# 2_MCU.net
KiCad netlist of a schematic drawn in Altium Designer
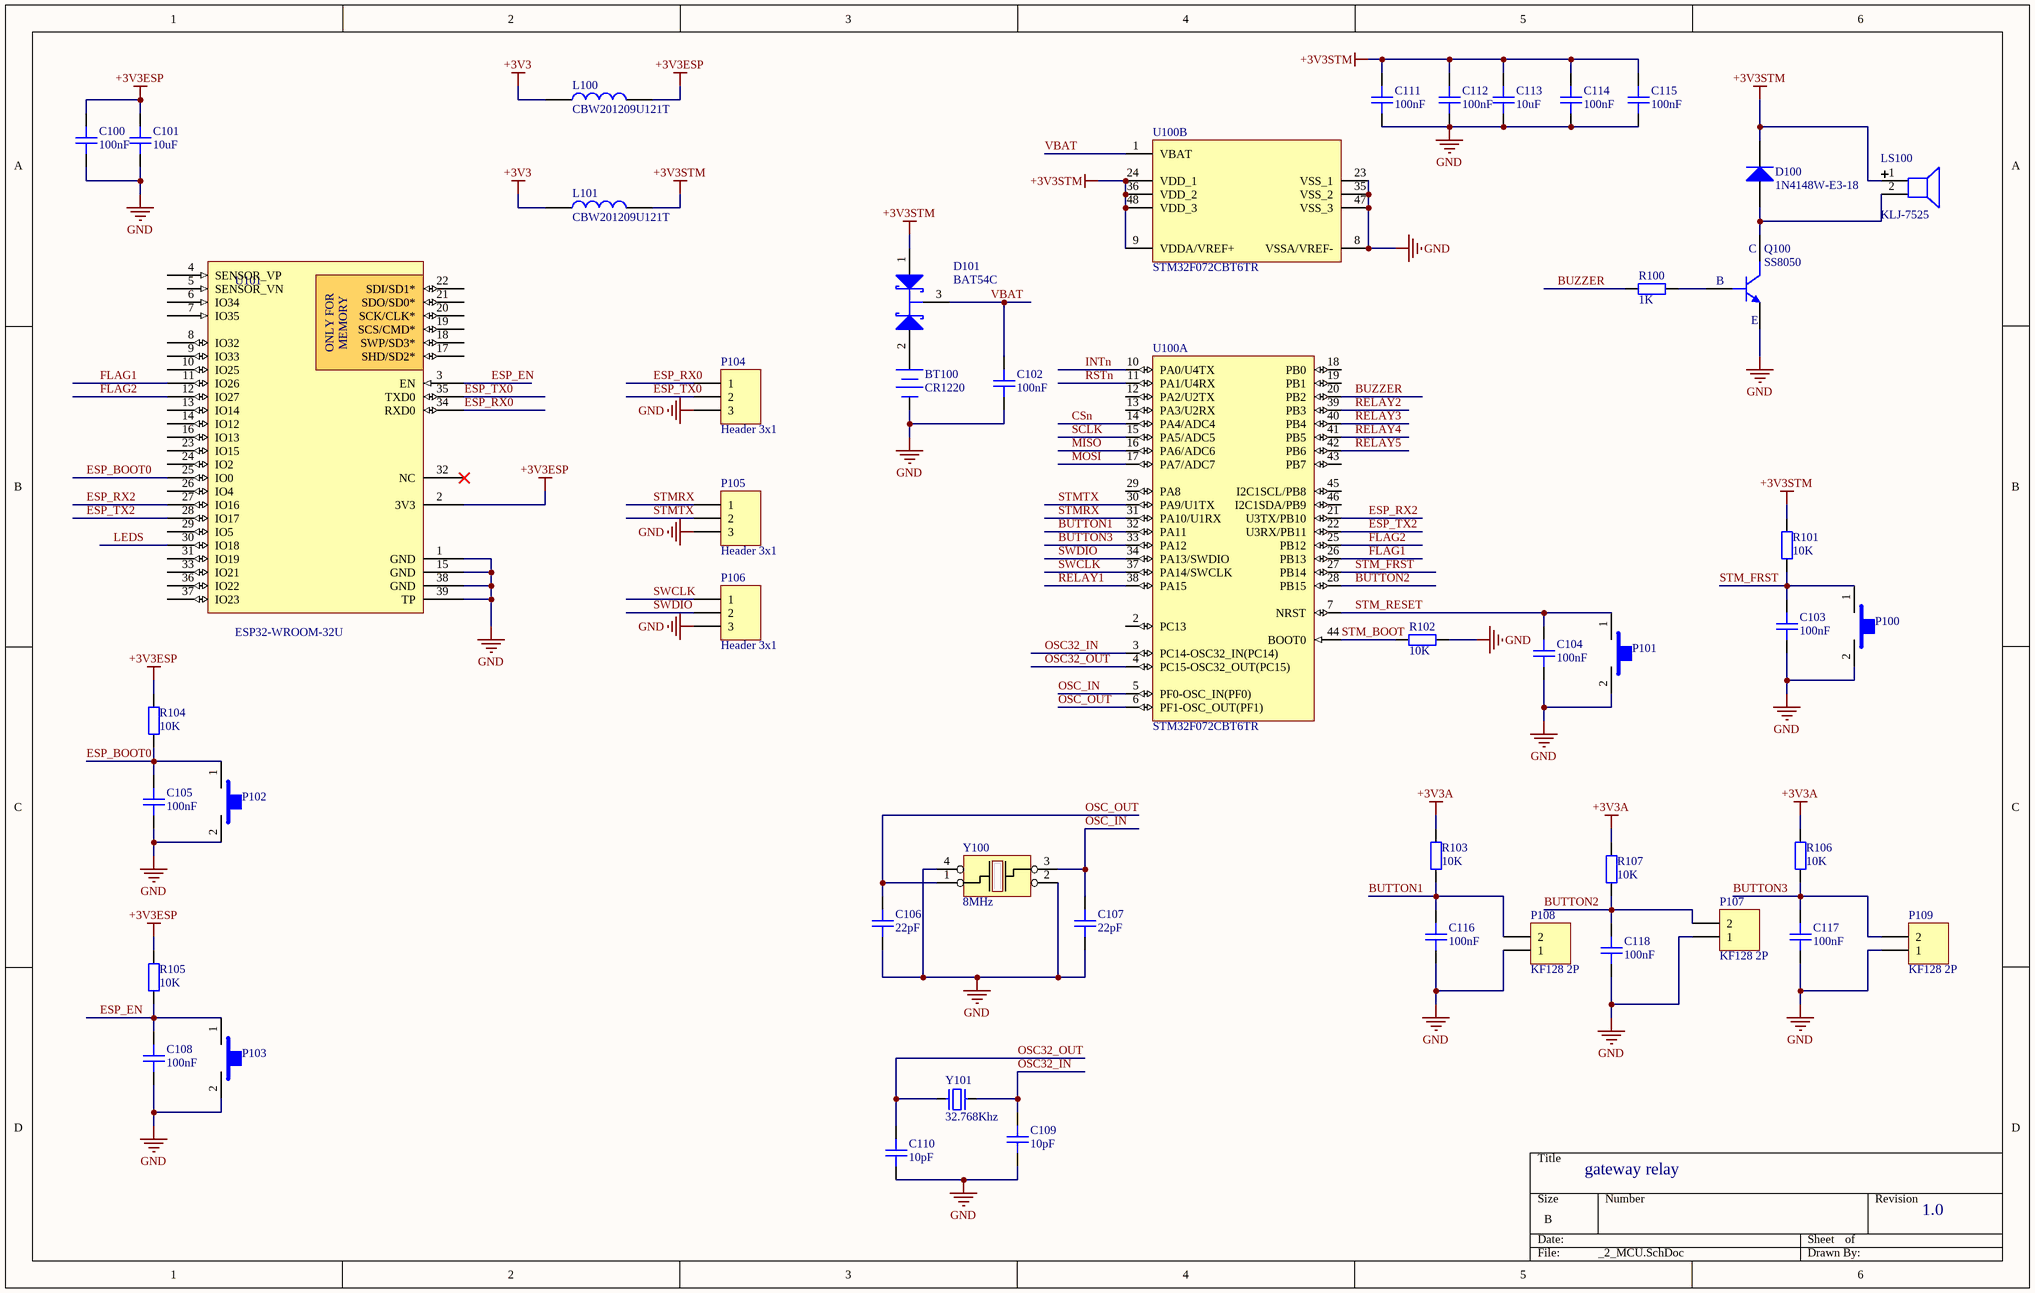
[diagram p0: _2_MCU.SchDoc]

(export (version "E")
  (design (tool "Eeschema 10.0.6"))
  (components
    (comp (ref "BT100")
      (value "CR1220")
      (footprint "PIN3V-CR1220")
      (description "Multicell Battery")
      (libsource (lib "BYTECH_HW_LIB_2019") (part "Battery CR1220"))
    )
    (comp (ref "C100")
      (value "100nF")
      (footprint "CAPC-0603 (1608)")
      (description "CAP CER 1uF 10% 16V X7R 0603")
      (fields (field (name "MPN") "CC0603KRX7R7BB105"))
      (libsource (lib "BYTECH_HW_LIB_2019") (part "CC0603KRX7R7BB105"))
    )
    (comp (ref "C101")
      (value "10uF")
      (footprint "CAPC-0603 (1608)")
      (description "CAP CER 0.018UF 50V X7R 0603")
      (fields (field (name "MPN") "CC0603JRX7R9BB183") (field (name "MFR") "Yageo"))
      (libsource (lib "BYTECH_HW_LIB_2019") (part "CC0603JRX7R9BB183"))
    )
    (comp (ref "C102")
      (value "100nF")
      (footprint "CAPC-0603 (1608)")
      (description "CAP CER 0.22UF 50V Y5V 0603")
      (fields (field (name "MPN") "CC0603ZRY5V9BB224"))
      (libsource (lib "BYTECH_HW_LIB_2019") (part "CC0603ZRY5V9BB224"))
    )
    (comp (ref "C103")
      (value "100nF")
      (footprint "CAPC-0603 (1608)")
      (description "CAP CER 0.22UF 50V Y5V 0603")
      (fields (field (name "MPN") "CC0603ZRY5V9BB224"))
      (libsource (lib "BYTECH_HW_LIB_2019") (part "CC0603ZRY5V9BB224"))
    )
    (comp (ref "C104")
      (value "100nF")
      (footprint "CAPC-0603 (1608)")
      (description "CAP CER 0.22UF 50V Y5V 0603")
      (fields (field (name "MPN") "CC0603ZRY5V9BB224"))
      (libsource (lib "BYTECH_HW_LIB_2019") (part "CC0603ZRY5V9BB224"))
    )
    (comp (ref "C105")
      (value "100nF")
      (footprint "CAPC-0603 (1608)")
      (description "CAP CER 0.22UF 50V Y5V 0603")
      (fields (field (name "MPN") "CC0603ZRY5V9BB224"))
      (libsource (lib "BYTECH_HW_LIB_2019") (part "CC0603ZRY5V9BB224"))
    )
    (comp (ref "C106")
      (value "22pF")
      (footprint "CAPC-0603 (1608)")
      (description "CAP CER 220PF 50V 5% COG/NPO 0603")
      (fields (field (name "MPN") "CC0603KRX7R9BB221"))
      (libsource (lib "BYTECH_HW_LIB_2019") (part "CC0603KRX7R9BB221"))
    )
    (comp (ref "C107")
      (value "22pF")
      (footprint "CAPC-0603 (1608)")
      (description "CAP CER 220PF 50V 5% COG/NPO 0603")
      (fields (field (name "MPN") "CC0603KRX7R9BB221"))
      (libsource (lib "BYTECH_HW_LIB_2019") (part "CC0603KRX7R9BB221"))
    )
    (comp (ref "C108")
      (value "100nF")
      (footprint "CAPC-0603 (1608)")
      (description "CAP CER 0.22UF 50V Y5V 0603")
      (fields (field (name "MPN") "CC0603ZRY5V9BB224"))
      (libsource (lib "BYTECH_HW_LIB_2019") (part "CC0603ZRY5V9BB224"))
    )
    (comp (ref "C109")
      (value "10pF")
      (footprint "CAPC-0603 (1608)")
      (description "CAP CER 2.2pF 50V +- 0.25pF COG/NPO 0603")
      (fields (field (name "MPN") "CC0603CRNPO9BN2R2"))
      (libsource (lib "BYTECH_HW_LIB_2019") (part "CC0603CRNPO9BN2R2"))
    )
    (comp (ref "C110")
      (value "10pF")
      (footprint "CAPC-0603 (1608)")
      (description "CAP CER 2.2pF 50V +- 0.25pF COG/NPO 0603")
      (fields (field (name "MPN") "CC0603CRNPO9BN2R2"))
      (libsource (lib "BYTECH_HW_LIB_2019") (part "CC0603CRNPO9BN2R2"))
    )
    (comp (ref "C111")
      (value "100nF")
      (footprint "CAPC-0603 (1608)")
      (description "CAP CER 1uF 10% 16V X7R 0603")
      (fields (field (name "MPN") "CC0603KRX7R7BB105"))
      (libsource (lib "BYTECH_HW_LIB_2019") (part "CC0603KRX7R7BB105"))
    )
    (comp (ref "C112")
      (value "100nF")
      (footprint "CAPC-0603 (1608)")
      (description "CAP CER 1uF 10% 16V X7R 0603")
      (fields (field (name "MPN") "CC0603KRX7R7BB105"))
      (libsource (lib "BYTECH_HW_LIB_2019") (part "CC0603KRX7R7BB105"))
    )
    (comp (ref "C113")
      (value "10uF")
      (footprint "CAPC-0603 (1608)")
      (description "CAP CER 0.018UF 50V X7R 0603")
      (fields (field (name "MPN") "CC0603JRX7R9BB183") (field (name "MFR") "Yageo"))
      (libsource (lib "BYTECH_HW_LIB_2019") (part "CC0603JRX7R9BB183"))
    )
    (comp (ref "C114")
      (value "100nF")
      (footprint "CAPC-0603 (1608)")
      (description "CAP CER 1uF 10% 16V X7R 0603")
      (fields (field (name "MPN") "CC0603KRX7R7BB105"))
      (libsource (lib "BYTECH_HW_LIB_2019") (part "CC0603KRX7R7BB105"))
    )
    (comp (ref "C115")
      (value "100nF")
      (footprint "CAPC-0603 (1608)")
      (description "CAP CER 1uF 10% 16V X7R 0603")
      (fields (field (name "MPN") "CC0603KRX7R7BB105"))
      (libsource (lib "BYTECH_HW_LIB_2019") (part "CC0603KRX7R7BB105"))
    )
    (comp (ref "C116")
      (value "100nF")
      (footprint "CAPC-0603 (1608)")
      (description "CAP CER 0.22UF 50V Y5V 0603")
      (fields (field (name "MPN") "CC0603ZRY5V9BB224"))
      (libsource (lib "BYTECH_HW_LIB_2019") (part "CC0603ZRY5V9BB224"))
    )
    (comp (ref "C117")
      (value "100nF")
      (footprint "CAPC-0603 (1608)")
      (description "CAP CER 0.22UF 50V Y5V 0603")
      (fields (field (name "MPN") "CC0603ZRY5V9BB224"))
      (libsource (lib "BYTECH_HW_LIB_2019") (part "CC0603ZRY5V9BB224"))
    )
    (comp (ref "C118")
      (value "100nF")
      (footprint "CAPC-0603 (1608)")
      (description "CAP CER 0.22UF 50V Y5V 0603")
      (fields (field (name "MPN") "CC0603ZRY5V9BB224"))
      (libsource (lib "BYTECH_HW_LIB_2019") (part "CC0603ZRY5V9BB224"))
    )
    (comp (ref "D100")
      (value "1N4148W-E3-18")
      (footprint "SOD-123")
      (description "DIODE GEN PURP 100V 300MA SOD123")
      (fields (field (name "MPN") "1N4148W-7-F") (field (name "MFR") "Diodes Incorporated"))
      (libsource (lib "BYTECH_HW_LIB_2019") (part "1N4148-W-7"))
    )
    (comp (ref "D101")
      (value "BAT54C")
      (footprint "SOT_23_3")
      (description "DIODE ARRAY SCHOTTKY 30V SOT23-3")
      (fields (field (name "MANUFACTURER") "On Semiconductor"))
      (libsource (lib "INSITUCOMPONENT") (part "DIO_BAT54C"))
    )
    (comp (ref "L100")
      (value "CBW201209U121T")
      (footprint "IND-0805 (2012)")
      (description "IND-FERRITE BEAD 220 OHM 0805 1LN")
      (fields (field (name "MPN") "MPZ2012S221A"))
      (libsource (lib "BYTECH_HW_LIB_2019") (part "MPZ2012S221A"))
    )
    (comp (ref "L101")
      (value "CBW201209U121T")
      (footprint "IND-0805 (2012)")
      (description "IND-FERRITE BEAD 220 OHM 0805 1LN")
      (fields (field (name "MPN") "MPZ2012S221A"))
      (libsource (lib "") (part "MPZ2012S221A_1"))
    )
    (comp (ref "LS100")
      (value "KLJ-7525")
      (footprint "KLJ-7525")
      (description "Dimension 75x75x25 mm")
      (libsource (lib "BYTECH_HW_LIB_2019") (part "KLJ-7525_BUZZER"))
    )
    (comp (ref "P100")
      (value "~")
      (footprint "SW 2P SMD")
      (description "SMD Mini Push Button Switch 2 Pin 3x6x2.7mm")
      (fields (field (name "MPN") "SMD Mini Push Button 2 SMD"))
      (libsource (lib "BYTECH_HW_LIB_2019") (part "Button 2 SMD"))
    )
    (comp (ref "P101")
      (value "~")
      (footprint "SW 2P SMD")
      (description "SMD Mini Push Button Switch 2 Pin 3x6x2.7mm")
      (fields (field (name "MPN") "SMD Mini Push Button 2 SMD"))
      (libsource (lib "BYTECH_HW_LIB_2019") (part "Button 2 SMD"))
    )
    (comp (ref "P102")
      (value "~")
      (footprint "SW 2P SMD")
      (description "SMD Mini Push Button Switch 2 Pin 3x6x2.7mm")
      (fields (field (name "MPN") "SMD Mini Push Button 2 SMD"))
      (libsource (lib "BYTECH_HW_LIB_2019") (part "Button 2 SMD"))
    )
    (comp (ref "P103")
      (value "~")
      (footprint "SW 2P SMD")
      (description "SMD Mini Push Button Switch 2 Pin 3x6x2.7mm")
      (fields (field (name "MPN") "SMD Mini Push Button 2 SMD"))
      (libsource (lib "BYTECH_HW_LIB_2019") (part "Button 2 SMD"))
    )
    (comp (ref "P104")
      (value "Header 3x1")
      (footprint "HDR1X3")
      (description "Header, 3-Pin, pitch 2.54mm")
      (libsource (lib "BYTECH_HW_LIB_2019") (part "Header 3x1"))
    )
    (comp (ref "P105")
      (value "Header 3x1")
      (footprint "HDR1X3")
      (description "Header, 3-Pin, pitch 2.54mm")
      (libsource (lib "BYTECH_HW_LIB_2019") (part "Header 3x1"))
    )
    (comp (ref "P106")
      (value "Header 3x1")
      (footprint "HDR1X3")
      (description "Header, 3-Pin, pitch 2.54mm")
      (libsource (lib "BYTECH_HW_LIB_2019") (part "Header 3x1"))
    )
    (comp (ref "P107")
      (value "KF128 2P")
      (footprint "KF128_2P")
      (description "Header, 2-Pin, pitch 5.08mm")
      (fields (field (name "MPN") "KF128-2P"))
      (libsource (lib "BYTECH_HW_LIB_2019") (part "KF128 2P"))
    )
    (comp (ref "P108")
      (value "KF128 2P")
      (footprint "KF128_2P")
      (description "Header, 2-Pin, pitch 5.08mm")
      (fields (field (name "MPN") "KF128-2P"))
      (libsource (lib "BYTECH_HW_LIB_2019") (part "KF128 2P"))
    )
    (comp (ref "P109")
      (value "KF128 2P")
      (footprint "KF128_2P")
      (description "Header, 2-Pin, pitch 5.08mm")
      (fields (field (name "MPN") "KF128-2P"))
      (libsource (lib "BYTECH_HW_LIB_2019") (part "KF128 2P"))
    )
    (comp (ref "Q100")
      (value "SS8050")
      (footprint "SOT23_3")
      (description "TRANS NPN 50V 0.15A SOT23-3")
      (fields (field (name "MPN") "2SC1815"))
      (libsource (lib "BYTECH_HW_LIB_2019") (part "2SC1815"))
    )
    (comp (ref "R100")
      (value "1K")
      (footprint "RESC-0603 (1608)")
      (description "RES SMD 1 KOHM 1% 1/10W 0603")
      (fields (field (name "MPN") "RC0603FR-071KL"))
      (libsource (lib "BYTECH_HW_LIB_2019") (part "RC0603FR-071KL"))
    )
    (comp (ref "R101")
      (value "10K")
      (footprint "RESC-0603 (1608)")
      (description "RES SMD 10K OHM 1% 1/10W 0603")
      (fields (field (name "MPN") "RC0603FR-0710KL"))
      (libsource (lib "BYTECH_HW_LIB_2019") (part "RC0603FR-0710KL"))
    )
    (comp (ref "R102")
      (value "10K")
      (footprint "RESC-0603 (1608)")
      (description "RES SMD 10K OHM 1% 1/10W 0603")
      (fields (field (name "MPN") "RC0603FR-0710KL"))
      (libsource (lib "") (part "RC0603FR-0710KL_1"))
    )
    (comp (ref "R103")
      (value "10K")
      (footprint "RESC-0603 (1608)")
      (description "RES SMD 10K OHM 1% 1/10W 0603")
      (fields (field (name "MPN") "RC0603FR-0710KL"))
      (libsource (lib "BYTECH_HW_LIB_2019") (part "RC0603FR-0710KL"))
    )
    (comp (ref "R104")
      (value "10K")
      (footprint "RESC-0603 (1608)")
      (description "RES SMD 10K OHM 1% 1/10W 0603")
      (fields (field (name "MPN") "RC0603FR-0710KL"))
      (libsource (lib "BYTECH_HW_LIB_2019") (part "RC0603FR-0710KL"))
    )
    (comp (ref "R105")
      (value "10K")
      (footprint "RESC-0603 (1608)")
      (description "RES SMD 10K OHM 1% 1/10W 0603")
      (fields (field (name "MPN") "RC0603FR-0710KL"))
      (libsource (lib "BYTECH_HW_LIB_2019") (part "RC0603FR-0710KL"))
    )
    (comp (ref "R106")
      (value "10K")
      (footprint "RESC-0603 (1608)")
      (description "RES SMD 10K OHM 1% 1/10W 0603")
      (fields (field (name "MPN") "RC0603FR-0710KL"))
      (libsource (lib "BYTECH_HW_LIB_2019") (part "RC0603FR-0710KL"))
    )
    (comp (ref "R107")
      (value "10K")
      (footprint "RESC-0603 (1608)")
      (description "RES SMD 10K OHM 1% 1/10W 0603")
      (fields (field (name "MPN") "RC0603FR-0710KL"))
      (libsource (lib "BYTECH_HW_LIB_2019") (part "RC0603FR-0710KL"))
    )
    (comp (ref "U100")
      (value "STM32F072CBT6TR")
      (footprint "LQFP-48")
      (description "IC MCU 32BIT 128KB FLASH 48LQFP")
      (fields (field (name "MFR") "STM"))
      (libsource (lib "BYTECH_HW_LIB_2019") (part "STM32F072CBT6"))
    )
    (comp (ref "U101")
      (value "ESP32-WROOM-32U")
      (footprint "ESP32-WROOM-32U")
      (description "Wi-Fi/BT BLE Module ESP32-D0WD")
      (fields (field (name "MFR") "Espressif"))
      (libsource (lib "BYTECH_HW_LIB_2019") (part "ESP32-WROOM-32U"))
    )
    (comp (ref "Y100")
      (value "8MHz")
      (footprint "CRYSTALL_SMD_3225")
      (description "CRYSTAL 24.0000MHZ 18PF SMD")
      (fields (field (name "MPN") "ABM8G-24.000MHZ-18-D2Y-T"))
      (libsource (lib "BYTECH_HW_LIB_2019") (part "ABM8G-24.000MHZ-18-D2Y-T"))
    )
    (comp (ref "Y101")
      (value "32.768Khz")
      (footprint "Thach Anh 2 Chan 32,768 KHz")
      (description "Crystal For all Crystal 2pin.")
      (libsource (lib "Altium_Lib_by_KhueNguyenCreator") (part "Thach Anh 2 chan 32,768 Khz"))
    )
  )
  (nets
    (net (code "1") (name "+3V3") (class "Default")
      (node (ref "L100") (pin "2") (pinfunction "2_2") (pintype "passive"))
      (node (ref "L101") (pin "1") (pinfunction "1_1") (pintype "passive"))
    )
    (net (code "2") (name "+3V3A") (class "Default")
      (node (ref "R103") (pin "2") (pinfunction "2_2") (pintype "passive"))
      (node (ref "R106") (pin "2") (pinfunction "2_2") (pintype "passive"))
      (node (ref "R107") (pin "2") (pinfunction "2_2") (pintype "passive"))
    )
    (net (code "3") (name "+3V3ESP") (class "Default")
      (node (ref "C100") (pin "2") (pinfunction "2_2") (pintype "passive"))
      (node (ref "C101") (pin "2") (pinfunction "2_2") (pintype "passive"))
      (node (ref "L100") (pin "1") (pinfunction "1_1") (pintype "passive"))
      (node (ref "R104") (pin "2") (pinfunction "2_2") (pintype "passive"))
      (node (ref "R105") (pin "2") (pinfunction "2_2") (pintype "passive"))
      (node (ref "U101") (pin "2") (pinfunction "3V3_2") (pintype "power_in"))
    )
    (net (code "4") (name "+3V3STM") (class "Default")
      (node (ref "C111") (pin "2") (pinfunction "2_2") (pintype "passive"))
      (node (ref "C112") (pin "2") (pinfunction "2_2") (pintype "passive"))
      (node (ref "C113") (pin "2") (pinfunction "2_2") (pintype "passive"))
      (node (ref "C114") (pin "2") (pinfunction "2_2") (pintype "passive"))
      (node (ref "C115") (pin "2") (pinfunction "2_2") (pintype "passive"))
      (node (ref "D100") (pin "2") (pinfunction "K_2") (pintype "passive"))
      (node (ref "D101") (pin "1") (pinfunction "A_1") (pintype "passive"))
      (node (ref "L101") (pin "2") (pinfunction "2_2") (pintype "passive"))
      (node (ref "LS100") (pin "1") (pinfunction "1_1") (pintype "passive"))
      (node (ref "R101") (pin "2") (pinfunction "2_2") (pintype "passive"))
      (node (ref "U100") (pin "24") (pinfunction "VDD_1_24") (pintype "power_in"))
      (node (ref "U100") (pin "36") (pinfunction "VDD_2_36") (pintype "power_in"))
      (node (ref "U100") (pin "48") (pinfunction "VDD_3_48") (pintype "power_in"))
      (node (ref "U100") (pin "9") (pinfunction "VDDA/VREF+_9") (pintype "power_in"))
    )
    (net (code "5") (name "/BUTTON1") (class "Default")
      (node (ref "C116") (pin "2") (pinfunction "2_2") (pintype "passive"))
      (node (ref "P108") (pin "2") (pinfunction "2_2") (pintype "passive"))
      (node (ref "R103") (pin "1") (pinfunction "1_1") (pintype "passive"))
      (node (ref "U100") (pin "32") (pinfunction "PA11_32") (pintype "bidirectional"))
    )
    (net (code "6") (name "/BUTTON2") (class "Default")
      (node (ref "C118") (pin "2") (pinfunction "2_2") (pintype "passive"))
      (node (ref "P107") (pin "2") (pinfunction "2_2") (pintype "passive"))
      (node (ref "R107") (pin "1") (pinfunction "1_1") (pintype "passive"))
      (node (ref "U100") (pin "28") (pinfunction "PB15_28") (pintype "bidirectional"))
    )
    (net (code "7") (name "/BUTTON3") (class "Default")
      (node (ref "C117") (pin "2") (pinfunction "2_2") (pintype "passive"))
      (node (ref "P109") (pin "2") (pinfunction "2_2") (pintype "passive"))
      (node (ref "R106") (pin "1") (pinfunction "1_1") (pintype "passive"))
      (node (ref "U100") (pin "33") (pinfunction "PA12_33") (pintype "bidirectional"))
    )
    (net (code "8") (name "/BUZZER") (class "Default")
      (node (ref "R100") (pin "2") (pinfunction "2_2") (pintype "passive"))
      (node (ref "U100") (pin "20") (pinfunction "PB2_20") (pintype "bidirectional"))
    )
    (net (code "9") (name "/CSn") (class "Default")
      (node (ref "U100") (pin "14") (pinfunction "PA4/ADC4_14") (pintype "bidirectional"))
    )
    (net (code "10") (name "/ESP_BOOT0") (class "Default")
      (node (ref "C105") (pin "2") (pinfunction "2_2") (pintype "passive"))
      (node (ref "P102") (pin "1") (pinfunction "1_1") (pintype "passive"))
      (node (ref "R104") (pin "1") (pinfunction "1_1") (pintype "passive"))
      (node (ref "U101") (pin "25") (pinfunction "IO0_25") (pintype "bidirectional"))
    )
    (net (code "11") (name "/ESP_EN") (class "Default")
      (node (ref "C108") (pin "2") (pinfunction "2_2") (pintype "passive"))
      (node (ref "P103") (pin "1") (pinfunction "1_1") (pintype "passive"))
      (node (ref "R105") (pin "1") (pinfunction "1_1") (pintype "passive"))
      (node (ref "U101") (pin "3") (pinfunction "EN_3") (pintype "input"))
    )
    (net (code "12") (name "/ESP_RX0") (class "Default")
      (node (ref "P104") (pin "1") (pinfunction "1_1") (pintype "passive"))
      (node (ref "U101") (pin "34") (pinfunction "RXD0_34") (pintype "bidirectional"))
    )
    (net (code "13") (name "/ESP_RX2") (class "Default")
      (node (ref "U100") (pin "21") (pinfunction "U3TX/PB10_21") (pintype "bidirectional"))
      (node (ref "U101") (pin "27") (pinfunction "IO16_27") (pintype "bidirectional"))
    )
    (net (code "14") (name "/ESP_TX0") (class "Default")
      (node (ref "P104") (pin "2") (pinfunction "2_2") (pintype "passive"))
      (node (ref "U101") (pin "35") (pinfunction "TXD0_35") (pintype "bidirectional"))
    )
    (net (code "15") (name "/ESP_TX2") (class "Default")
      (node (ref "U100") (pin "22") (pinfunction "U3RX/PB11_22") (pintype "bidirectional"))
      (node (ref "U101") (pin "28") (pinfunction "IO17_28") (pintype "bidirectional"))
    )
    (net (code "16") (name "/FLAG1") (class "Default")
      (node (ref "U100") (pin "26") (pinfunction "PB13_26") (pintype "bidirectional"))
      (node (ref "U101") (pin "11") (pinfunction "IO26_11") (pintype "bidirectional"))
    )
    (net (code "17") (name "/FLAG2") (class "Default")
      (node (ref "U100") (pin "25") (pinfunction "PB12_25") (pintype "bidirectional"))
      (node (ref "U101") (pin "12") (pinfunction "IO27_12") (pintype "bidirectional"))
    )
    (net (code "18") (name "/INTn") (class "Default")
      (node (ref "U100") (pin "10") (pinfunction "PA0/U4TX_10") (pintype "bidirectional"))
    )
    (net (code "19") (name "/LEDS") (class "Default")
      (node (ref "U101") (pin "30") (pinfunction "IO18_30") (pintype "bidirectional"))
    )
    (net (code "20") (name "/MISO") (class "Default")
      (node (ref "U100") (pin "16") (pinfunction "PA6/ADC6_16") (pintype "bidirectional"))
    )
    (net (code "21") (name "/MOSI") (class "Default")
      (node (ref "U100") (pin "17") (pinfunction "PA7/ADC7_17") (pintype "bidirectional"))
    )
    (net (code "22") (name "/OSC32_IN") (class "Default")
      (node (ref "C109") (pin "2") (pinfunction "2_2") (pintype "passive"))
      (node (ref "U100") (pin "3") (pinfunction "PC14-OSC32_IN(PC14)_3") (pintype "bidirectional"))
      (node (ref "Y101") (pin "2") (pinfunction "2_2") (pintype "passive"))
    )
    (net (code "23") (name "/OSC32_OUT") (class "Default")
      (node (ref "C110") (pin "2") (pinfunction "2_2") (pintype "passive"))
      (node (ref "U100") (pin "4") (pinfunction "PC15-OSC32_OUT(PC15)_4") (pintype "bidirectional"))
      (node (ref "Y101") (pin "1") (pinfunction "1_1") (pintype "passive"))
    )
    (net (code "24") (name "/OSC_IN") (class "Default")
      (node (ref "C107") (pin "2") (pinfunction "2_2") (pintype "passive"))
      (node (ref "U100") (pin "5") (pinfunction "PF0-OSC_IN(PF0)_5") (pintype "bidirectional"))
      (node (ref "Y100") (pin "3") (pinfunction "3_3") (pintype "passive"))
    )
    (net (code "25") (name "/OSC_OUT") (class "Default")
      (node (ref "C106") (pin "2") (pinfunction "2_2") (pintype "passive"))
      (node (ref "U100") (pin "6") (pinfunction "PF1-OSC_OUT(PF1)_6") (pintype "bidirectional"))
      (node (ref "Y100") (pin "1") (pinfunction "1_1") (pintype "passive"))
    )
    (net (code "26") (name "/RELAY1") (class "Default")
      (node (ref "U100") (pin "38") (pinfunction "PA15_38") (pintype "bidirectional"))
    )
    (net (code "27") (name "/RELAY2") (class "Default")
      (node (ref "U100") (pin "39") (pinfunction "PB3_39") (pintype "bidirectional"))
    )
    (net (code "28") (name "/RELAY3") (class "Default")
      (node (ref "U100") (pin "40") (pinfunction "PB4_40") (pintype "bidirectional"))
    )
    (net (code "29") (name "/RELAY4") (class "Default")
      (node (ref "U100") (pin "41") (pinfunction "PB5_41") (pintype "bidirectional"))
    )
    (net (code "30") (name "/RELAY5") (class "Default")
      (node (ref "U100") (pin "42") (pinfunction "PB6_42") (pintype "bidirectional"))
    )
    (net (code "31") (name "/RSTn") (class "Default")
      (node (ref "U100") (pin "11") (pinfunction "PA1/U4RX_11") (pintype "bidirectional"))
    )
    (net (code "32") (name "/SCLK") (class "Default")
      (node (ref "U100") (pin "15") (pinfunction "PA5/ADC5_15") (pintype "bidirectional"))
    )
    (net (code "33") (name "/STMRX") (class "Default")
      (node (ref "P105") (pin "1") (pinfunction "1_1") (pintype "passive"))
      (node (ref "U100") (pin "31") (pinfunction "PA10/U1RX_31") (pintype "bidirectional"))
    )
    (net (code "34") (name "/STMTX") (class "Default")
      (node (ref "P105") (pin "2") (pinfunction "2_2") (pintype "passive"))
      (node (ref "U100") (pin "30") (pinfunction "PA9/U1TX_30") (pintype "bidirectional"))
    )
    (net (code "35") (name "/STM_BOOT") (class "Default")
      (node (ref "R102") (pin "2") (pinfunction "2_2") (pintype "passive"))
      (node (ref "U100") (pin "44") (pinfunction "BOOT0_44") (pintype "input"))
    )
    (net (code "36") (name "/STM_FRST") (class "Default")
      (node (ref "C103") (pin "2") (pinfunction "2_2") (pintype "passive"))
      (node (ref "P100") (pin "1") (pinfunction "1_1") (pintype "passive"))
      (node (ref "R101") (pin "1") (pinfunction "1_1") (pintype "passive"))
      (node (ref "U100") (pin "27") (pinfunction "PB14_27") (pintype "bidirectional"))
    )
    (net (code "37") (name "/STM_RESET") (class "Default")
      (node (ref "C104") (pin "2") (pinfunction "2_2") (pintype "passive"))
      (node (ref "P101") (pin "1") (pinfunction "1_1") (pintype "passive"))
      (node (ref "U100") (pin "7") (pinfunction "NRST_7") (pintype "bidirectional"))
    )
    (net (code "38") (name "/SWCLK") (class "Default")
      (node (ref "P106") (pin "1") (pinfunction "1_1") (pintype "passive"))
      (node (ref "U100") (pin "37") (pinfunction "PA14/SWCLK_37") (pintype "bidirectional"))
    )
    (net (code "39") (name "/SWDIO") (class "Default")
      (node (ref "P106") (pin "2") (pinfunction "2_2") (pintype "passive"))
      (node (ref "U100") (pin "34") (pinfunction "PA13/SWDIO_34") (pintype "bidirectional"))
    )
    (net (code "40") (name "/VBAT") (class "Default")
      (node (ref "C102") (pin "2") (pinfunction "2_2") (pintype "passive"))
      (node (ref "D101") (pin "3") (pinfunction "K_3") (pintype "passive"))
      (node (ref "U100") (pin "1") (pinfunction "VBAT_1") (pintype "power_in"))
    )
    (net (code "41") (name "GND") (class "Default")
      (node (ref "BT100") (pin "2") (pinfunction "-_2") (pintype "passive"))
      (node (ref "C100") (pin "1") (pinfunction "1_1") (pintype "passive"))
      (node (ref "C101") (pin "1") (pinfunction "1_1") (pintype "passive"))
      (node (ref "C102") (pin "1") (pinfunction "1_1") (pintype "passive"))
      (node (ref "C103") (pin "1") (pinfunction "1_1") (pintype "passive"))
      (node (ref "C104") (pin "1") (pinfunction "1_1") (pintype "passive"))
      (node (ref "C105") (pin "1") (pinfunction "1_1") (pintype "passive"))
      (node (ref "C106") (pin "1") (pinfunction "1_1") (pintype "passive"))
      (node (ref "C107") (pin "1") (pinfunction "1_1") (pintype "passive"))
      (node (ref "C108") (pin "1") (pinfunction "1_1") (pintype "passive"))
      (node (ref "C109") (pin "1") (pinfunction "1_1") (pintype "passive"))
      (node (ref "C110") (pin "1") (pinfunction "1_1") (pintype "passive"))
      (node (ref "C111") (pin "1") (pinfunction "1_1") (pintype "passive"))
      (node (ref "C112") (pin "1") (pinfunction "1_1") (pintype "passive"))
      (node (ref "C113") (pin "1") (pinfunction "1_1") (pintype "passive"))
      (node (ref "C114") (pin "1") (pinfunction "1_1") (pintype "passive"))
      (node (ref "C115") (pin "1") (pinfunction "1_1") (pintype "passive"))
      (node (ref "C116") (pin "1") (pinfunction "1_1") (pintype "passive"))
      (node (ref "C117") (pin "1") (pinfunction "1_1") (pintype "passive"))
      (node (ref "C118") (pin "1") (pinfunction "1_1") (pintype "passive"))
      (node (ref "P100") (pin "2") (pinfunction "2_2") (pintype "passive"))
      (node (ref "P101") (pin "2") (pinfunction "2_2") (pintype "passive"))
      (node (ref "P102") (pin "2") (pinfunction "2_2") (pintype "passive"))
      (node (ref "P103") (pin "2") (pinfunction "2_2") (pintype "passive"))
      (node (ref "P104") (pin "3") (pinfunction "3_3") (pintype "passive"))
      (node (ref "P105") (pin "3") (pinfunction "3_3") (pintype "passive"))
      (node (ref "P106") (pin "3") (pinfunction "3_3") (pintype "passive"))
      (node (ref "P107") (pin "1") (pinfunction "1_1") (pintype "passive"))
      (node (ref "P108") (pin "1") (pinfunction "1_1") (pintype "passive"))
      (node (ref "P109") (pin "1") (pinfunction "1_1") (pintype "passive"))
      (node (ref "Q100") (pin "2") (pinfunction "E_2") (pintype "passive"))
      (node (ref "R102") (pin "1") (pinfunction "1_1") (pintype "passive"))
      (node (ref "U100") (pin "23") (pinfunction "VSS_1_23") (pintype "power_in"))
      (node (ref "U100") (pin "35") (pinfunction "VSS_2_35") (pintype "power_in"))
      (node (ref "U100") (pin "47") (pinfunction "VSS_3_47") (pintype "power_in"))
      (node (ref "U100") (pin "8") (pinfunction "VSSA/VREF-_8") (pintype "power_in"))
      (node (ref "U101") (pin "1") (pinfunction "GND_1") (pintype "power_in"))
      (node (ref "U101") (pin "15") (pinfunction "GND_15") (pintype "power_in"))
      (node (ref "U101") (pin "38") (pinfunction "GND_38") (pintype "power_in"))
      (node (ref "U101") (pin "39") (pinfunction "TP_39") (pintype "power_in"))
      (node (ref "Y100") (pin "2") (pinfunction "2_2") (pintype "passive"))
      (node (ref "Y100") (pin "4") (pinfunction "4_4") (pintype "passive"))
    )
    (net (code "42") (name "Net-(BT100-+)") (class "Default")
      (node (ref "BT100") (pin "1") (pinfunction "+_1") (pintype "passive"))
      (node (ref "D101") (pin "2") (pinfunction "A_2") (pintype "passive"))
    )
    (net (code "43") (name "Net-(D100-A)") (class "Default")
      (node (ref "D100") (pin "1") (pinfunction "A_1") (pintype "passive"))
      (node (ref "LS100") (pin "2") (pinfunction "2_2") (pintype "passive"))
      (node (ref "Q100") (pin "3") (pinfunction "C_3") (pintype "passive"))
    )
    (net (code "44") (name "Net-(Q100-B)") (class "Default")
      (node (ref "Q100") (pin "1") (pinfunction "B_1") (pintype "passive"))
      (node (ref "R100") (pin "1") (pinfunction "1_1") (pintype "passive"))
    )
    (net (code "45") (name "unconnected-(U100A-I2C1SCL{slash}PB8-Pad45)") (class "Default")
      (node (ref "U100") (pin "45") (pinfunction "I2C1SCL/PB8_45") (pintype "bidirectional"))
    )
    (net (code "46") (name "unconnected-(U100A-I2C1SDA{slash}PB9-Pad46)") (class "Default")
      (node (ref "U100") (pin "46") (pinfunction "I2C1SDA/PB9_46") (pintype "bidirectional"))
    )
    (net (code "47") (name "unconnected-(U100A-PA2{slash}U2TX-Pad12)") (class "Default")
      (node (ref "U100") (pin "12") (pinfunction "PA2/U2TX_12") (pintype "bidirectional"))
    )
    (net (code "48") (name "unconnected-(U100A-PA3{slash}U2RX-Pad13)") (class "Default")
      (node (ref "U100") (pin "13") (pinfunction "PA3/U2RX_13") (pintype "bidirectional"))
    )
    (net (code "49") (name "unconnected-(U100A-PA8-Pad29)") (class "Default")
      (node (ref "U100") (pin "29") (pinfunction "PA8_29") (pintype "bidirectional"))
    )
    (net (code "50") (name "unconnected-(U100A-PB0-Pad18)") (class "Default")
      (node (ref "U100") (pin "18") (pinfunction "PB0_18") (pintype "bidirectional"))
    )
    (net (code "51") (name "unconnected-(U100A-PB1-Pad19)") (class "Default")
      (node (ref "U100") (pin "19") (pinfunction "PB1_19") (pintype "bidirectional"))
    )
    (net (code "52") (name "unconnected-(U100A-PB7-Pad43)") (class "Default")
      (node (ref "U100") (pin "43") (pinfunction "PB7_43") (pintype "bidirectional"))
    )
    (net (code "53") (name "unconnected-(U100A-PC13-Pad2)") (class "Default")
      (node (ref "U100") (pin "2") (pinfunction "PC13_2") (pintype "bidirectional"))
    )
    (net (code "54") (name "unconnected-(U101-IO2-Pad24)") (class "Default")
      (node (ref "U101") (pin "24") (pinfunction "IO2_24") (pintype "bidirectional"))
    )
    (net (code "55") (name "unconnected-(U101-IO4-Pad26)") (class "Default")
      (node (ref "U101") (pin "26") (pinfunction "IO4_26") (pintype "bidirectional"))
    )
    (net (code "56") (name "unconnected-(U101-IO5-Pad29)") (class "Default")
      (node (ref "U101") (pin "29") (pinfunction "IO5_29") (pintype "bidirectional"))
    )
    (net (code "57") (name "unconnected-(U101-IO12-Pad14)") (class "Default")
      (node (ref "U101") (pin "14") (pinfunction "IO12_14") (pintype "bidirectional"))
    )
    (net (code "58") (name "unconnected-(U101-IO13-Pad16)") (class "Default")
      (node (ref "U101") (pin "16") (pinfunction "IO13_16") (pintype "bidirectional"))
    )
    (net (code "59") (name "unconnected-(U101-IO14-Pad13)") (class "Default")
      (node (ref "U101") (pin "13") (pinfunction "IO14_13") (pintype "bidirectional"))
    )
    (net (code "60") (name "unconnected-(U101-IO15-Pad23)") (class "Default")
      (node (ref "U101") (pin "23") (pinfunction "IO15_23") (pintype "bidirectional"))
    )
    (net (code "61") (name "unconnected-(U101-IO19-Pad31)") (class "Default")
      (node (ref "U101") (pin "31") (pinfunction "IO19_31") (pintype "bidirectional"))
    )
    (net (code "62") (name "unconnected-(U101-IO21-Pad33)") (class "Default")
      (node (ref "U101") (pin "33") (pinfunction "IO21_33") (pintype "bidirectional"))
    )
    (net (code "63") (name "unconnected-(U101-IO22-Pad36)") (class "Default")
      (node (ref "U101") (pin "36") (pinfunction "IO22_36") (pintype "bidirectional"))
    )
    (net (code "64") (name "unconnected-(U101-IO23-Pad37)") (class "Default")
      (node (ref "U101") (pin "37") (pinfunction "IO23_37") (pintype "bidirectional"))
    )
    (net (code "65") (name "unconnected-(U101-IO25-Pad10)") (class "Default")
      (node (ref "U101") (pin "10") (pinfunction "IO25_10") (pintype "bidirectional"))
    )
    (net (code "66") (name "unconnected-(U101-IO32-Pad8)") (class "Default")
      (node (ref "U101") (pin "8") (pinfunction "IO32_8") (pintype "bidirectional"))
    )
    (net (code "67") (name "unconnected-(U101-IO33-Pad9)") (class "Default")
      (node (ref "U101") (pin "9") (pinfunction "IO33_9") (pintype "bidirectional"))
    )
    (net (code "68") (name "unconnected-(U101-IO34-Pad6)") (class "Default")
      (node (ref "U101") (pin "6") (pinfunction "IO34_6") (pintype "input"))
    )
    (net (code "69") (name "unconnected-(U101-IO35-Pad7)") (class "Default")
      (node (ref "U101") (pin "7") (pinfunction "IO35_7") (pintype "input"))
    )
    (net (code "70") (name "unconnected-(U101-NC-Pad32)") (class "Default")
      (node (ref "U101") (pin "32") (pinfunction "NC_32") (pintype "passive+no_connect"))
    )
    (net (code "71") (name "unconnected-(U101-SCK{slash}CLK*-Pad20)") (class "Default")
      (node (ref "U101") (pin "20") (pinfunction "SCK/CLK*_20") (pintype "bidirectional"))
    )
    (net (code "72") (name "unconnected-(U101-SCS{slash}CMD*-Pad19)") (class "Default")
      (node (ref "U101") (pin "19") (pinfunction "SCS/CMD*_19") (pintype "bidirectional"))
    )
    (net (code "73") (name "unconnected-(U101-SDI{slash}SD1*-Pad22)") (class "Default")
      (node (ref "U101") (pin "22") (pinfunction "SDI/SD1*_22") (pintype "bidirectional"))
    )
    (net (code "74") (name "unconnected-(U101-SDO{slash}SD0*-Pad21)") (class "Default")
      (node (ref "U101") (pin "21") (pinfunction "SDO/SD0*_21") (pintype "bidirectional"))
    )
    (net (code "75") (name "unconnected-(U101-SENSOR_VN-Pad5)") (class "Default")
      (node (ref "U101") (pin "5") (pinfunction "SENSOR_VN_5") (pintype "input"))
    )
    (net (code "76") (name "unconnected-(U101-SENSOR_VP-Pad4)") (class "Default")
      (node (ref "U101") (pin "4") (pinfunction "SENSOR_VP_4") (pintype "input"))
    )
    (net (code "77") (name "unconnected-(U101-SHD{slash}SD2*-Pad17)") (class "Default")
      (node (ref "U101") (pin "17") (pinfunction "SHD/SD2*_17") (pintype "bidirectional"))
    )
    (net (code "78") (name "unconnected-(U101-SWP{slash}SD3*-Pad18)") (class "Default")
      (node (ref "U101") (pin "18") (pinfunction "SWP/SD3*_18") (pintype "bidirectional"))
    )
  )
)
